# Power_Sheet.net
KiCad netlist of a schematic drawn in Altium Designer
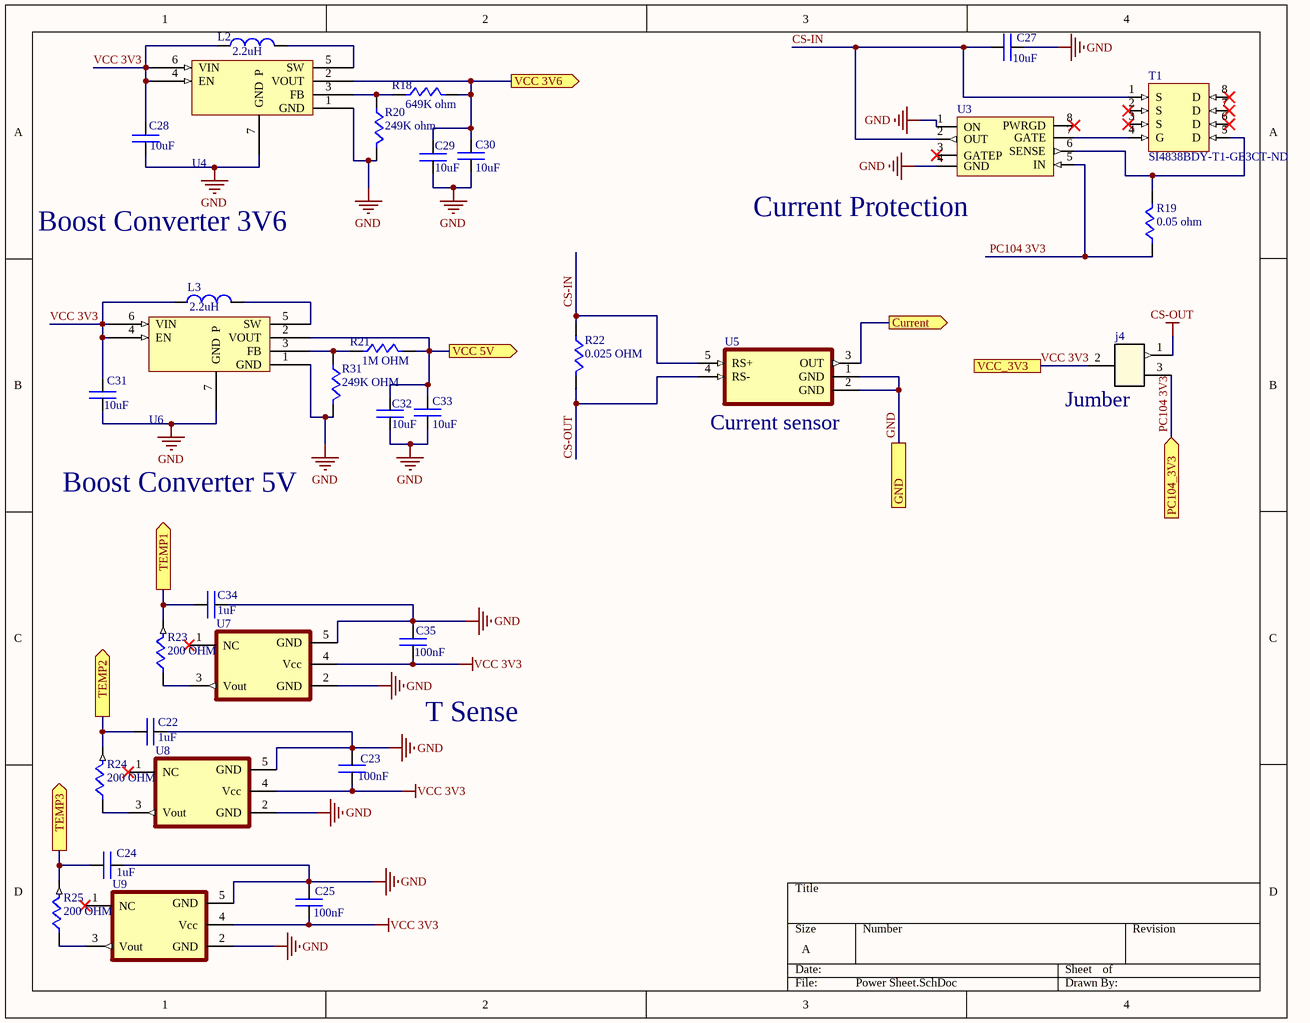
[diagram p0: Power Sheet.SchDoc]

(export (version "E")
  (design (tool "Eeschema 10.0.6"))
  (components
    (comp (ref "C22")
      (value "CAP CER 1UF 16V X7R 0805")
      (footprint "0805 C")
      (description "1µF ±5% 16V Ceramic Capacitor X7R 0805 (2012 Metric)")
      (fields
        (field (name "MANUFACTURER") "Murata")
        (field (name "MANUFACTURER PART NUMBER") "GRM219R61H105KA73D")
        (field (name "CAPACITANCE") "1uF")
      )
      (libsource (lib "comm sub") (part "C_1uF"))
    )
    (comp (ref "C23")
      (value "CAP CER 0.1UF 10V 0805")
      (footprint "0805 C")
      (description "0.1µF ±10% 16V Ceramic Capacitor X7R 0805 (2012 Metric)")
      (fields
        (field (name "MANUFACTURER") "Johanson")
        (field (name "MANUFACTURER PART NUMBER") "160R15W104KV4T")
        (field (name "CAPACITANCE") "100nF")
      )
      (libsource (lib "comm sub") (part "C_100nF"))
    )
    (comp (ref "C24")
      (value "CAP CER 1UF 16V X7R 0805")
      (footprint "0805 C")
      (description "1µF ±5% 16V Ceramic Capacitor X7R 0805 (2012 Metric)")
      (fields
        (field (name "MANUFACTURER") "Murata")
        (field (name "MANUFACTURER PART NUMBER") "GRM219R61H105KA73D")
        (field (name "CAPACITANCE") "1uF")
      )
      (libsource (lib "comm sub") (part "C_1uF"))
    )
    (comp (ref "C25")
      (value "CAP CER 0.1UF 10V 0805")
      (footprint "0805 C")
      (description "0.1µF ±10% 16V Ceramic Capacitor X7R 0805 (2012 Metric)")
      (fields
        (field (name "MANUFACTURER") "Johanson")
        (field (name "MANUFACTURER PART NUMBER") "160R15W104KV4T")
        (field (name "CAPACITANCE") "100nF")
      )
      (libsource (lib "comm sub") (part "C_100nF"))
    )
    (comp (ref "C27")
      (value "CAP CER 10UF 10V X5R 0805")
      (footprint "0805 C")
      (description "10µF ±10% 10V Ceramic Capacitor X5R 0805 (2012 Metric)")
      (fields
        (field (name "MANUFACTURER") "TDK")
        (field (name "MANUFACTURER PART NUMBER") "C2012X5R1C106K085AC")
        (field (name "CAPACITANCE") "10uF")
      )
      (libsource (lib "comm sub") (part "C_10uF"))
    )
    (comp (ref "C28")
      (value "CAP CER 10UF 10V X5R 0805")
      (footprint "0805 C")
      (description "10µF ±10% 10V Ceramic Capacitor X5R 0805 (2012 Metric)")
      (fields
        (field (name "MANUFACTURER") "TDK")
        (field (name "MANUFACTURER PART NUMBER") "C2012X5R1C106K085AC")
        (field (name "CAPACITANCE") "10uF")
      )
      (libsource (lib "comm sub") (part "C_10uF"))
    )
    (comp (ref "C29")
      (value "CAP CER 10UF 10V X5R 0805")
      (footprint "0805 C")
      (description "10µF ±10% 10V Ceramic Capacitor X5R 0805 (2012 Metric)")
      (fields
        (field (name "MANUFACTURER") "TDK")
        (field (name "MANUFACTURER PART NUMBER") "C2012X5R1C106K085AC")
        (field (name "CAPACITANCE") "10uF")
      )
      (libsource (lib "comm sub") (part "C_10uF"))
    )
    (comp (ref "C30")
      (value "CAP CER 10UF 10V X5R 0805")
      (footprint "0805 C")
      (description "10µF ±10% 10V Ceramic Capacitor X5R 0805 (2012 Metric)")
      (fields
        (field (name "MANUFACTURER") "TDK")
        (field (name "MANUFACTURER PART NUMBER") "C2012X5R1C106K085AC")
        (field (name "CAPACITANCE") "10uF")
      )
      (libsource (lib "comm sub") (part "C_10uF"))
    )
    (comp (ref "C31")
      (value "CAP CER 10UF 10V X5R 0805")
      (footprint "0805 C")
      (description "10µF ±10% 10V Ceramic Capacitor X5R 0805 (2012 Metric)")
      (fields
        (field (name "MANUFACTURER") "TDK")
        (field (name "MANUFACTURER PART NUMBER") "C2012X5R1C106K085AC")
        (field (name "CAPACITANCE") "10uF")
      )
      (libsource (lib "comm sub") (part "C_10uF"))
    )
    (comp (ref "C32")
      (value "CAP CER 10UF 10V X5R 0805")
      (footprint "0805 C")
      (description "10µF ±10% 10V Ceramic Capacitor X5R 0805 (2012 Metric)")
      (fields
        (field (name "MANUFACTURER") "TDK")
        (field (name "MANUFACTURER PART NUMBER") "C2012X5R1C106K085AC")
        (field (name "CAPACITANCE") "10uF")
      )
      (libsource (lib "comm sub") (part "C_10uF"))
    )
    (comp (ref "C33")
      (value "CAP CER 10UF 10V X5R 0805")
      (footprint "0805 C")
      (description "10µF ±10% 10V Ceramic Capacitor X5R 0805 (2012 Metric)")
      (fields
        (field (name "MANUFACTURER") "TDK")
        (field (name "MANUFACTURER PART NUMBER") "C2012X5R1C106K085AC")
        (field (name "CAPACITANCE") "10uF")
      )
      (libsource (lib "comm sub") (part "C_10uF"))
    )
    (comp (ref "C34")
      (value "CAP CER 1UF 16V X7R 0805")
      (footprint "0805 C")
      (description "1µF ±5% 16V Ceramic Capacitor X7R 0805 (2012 Metric)")
      (fields
        (field (name "MANUFACTURER") "Murata")
        (field (name "MANUFACTURER PART NUMBER") "GRM219R61H105KA73D")
        (field (name "CAPACITANCE") "1uF")
      )
      (libsource (lib "comm sub") (part "C_1uF"))
    )
    (comp (ref "C35")
      (value "CAP CER 0.1UF 10V 0805")
      (footprint "0805 C")
      (description "0.1µF ±10% 16V Ceramic Capacitor X7R 0805 (2012 Metric)")
      (fields
        (field (name "MANUFACTURER") "Johanson")
        (field (name "MANUFACTURER PART NUMBER") "160R15W104KV4T")
        (field (name "CAPACITANCE") "100nF")
      )
      (libsource (lib "comm sub") (part "C_100nF"))
    )
    (comp (ref "j4")
      (value "CONN HEADER VERT 3POS 2.54MM")
      (footprint "jumber")
      (description "Connector Header Through Hole 3 position 0.100\" (2.54mm)")
      (fields (field (name "MANUFACTURER") "Harwin") (field (name "MANUFACTURER PART NUMBER") "M20-9990345"))
      (libsource (lib "comm sub") (part "jumber"))
    )
    (comp (ref "L2")
      (value "FIXED IND 2.2UH 800MA 200 MOHM")
      (footprint "0805 L")
      (description "2.2µH Shielded Multilayer Inductor 800mA 200mOhm Max 0805 (2012 Metric)")
      (fields
        (field (name "MANUFACTURER") "Taiyo Yuden")
        (field (name "MANUFACTURER PART NUMBER") "BRC2012T2R2MD")
        (field (name "INDUCTANCE") "2.2uH")
      )
      (libsource (lib "comm sub") (part "L _2.2 uh"))
    )
    (comp (ref "L3")
      (value "FIXED IND 2.2UH 800MA 200 MOHM")
      (footprint "0805 L")
      (description "2.2µH Shielded Multilayer Inductor 800mA 200mOhm Max 0805 (2012 Metric)")
      (fields
        (field (name "MANUFACTURER") "Taiyo Yuden")
        (field (name "MANUFACTURER PART NUMBER") "BRC2012T2R2MD")
        (field (name "INDUCTANCE") "2.2uH")
      )
      (libsource (lib "comm sub") (part "L _2.2 uh"))
    )
    (comp (ref "R18")
      (value "649K ohm")
      (footprint "0805 R")
      (fields
        (field (name "MANUFACTURER") "Vishay")
        (field (name "MANUFACTURER PART NUMBER") "CRCW08050000Z0EAC")
        (field (name "TOLERANCE") "0.5%")
      )
      (libsource (lib "comm sub") (part "R_649k ohm"))
    )
    (comp (ref "R19")
      (value "0.05 ohm")
      (footprint "0805 R")
      (fields
        (field (name "MANUFACTURER") "Vishay")
        (field (name "MANUFACTURER PART NUMBER") "CRCW08050000Z0EAC")
        (field (name "TOLERANCE") "1%")
      )
      (libsource (lib "comm sub") (part "R_0.05ohm"))
    )
    (comp (ref "R20")
      (value "249K ohm")
      (footprint "0805 R")
      (fields
        (field (name "MANUFACTURER") "Vishay Dale")
        (field (name "MANUFACTURER PART NUMBER") "CRCW0805249KFKEAHP")
        (field (name "TOLERANCE") "1%")
      )
      (libsource (lib "comm sub") (part "R_249 kohm"))
    )
    (comp (ref "R21")
      (value "1M OHM")
      (footprint "0805 R")
      (fields
        (field (name "MANUFACTURER") "Vishay")
        (field (name "MANUFACTURER PART NUMBER") "CRCW08050000Z0EAC")
        (field (name "TOLERANCE") "1%")
      )
      (libsource (lib "comm sub") (part "R_1 Mohm"))
    )
    (comp (ref "R22")
      (value "0.025 OHM")
      (footprint "0805 R")
      (fields
        (field (name "MANUFACTURER") "Vishay")
        (field (name "MANUFACTURER PART NUMBER") "CRCW08050000Z0EAC")
      )
      (libsource (lib "comm sub") (part "R_0.025ohm"))
    )
    (comp (ref "R23")
      (value "200 OHM")
      (footprint "0805 R")
      (description "200 Ohms ±0.1% 0.125W, 1/8W Chip Resistor 0805 (2012 Metric) Automotive AEC-Q200 Thin Film")
      (fields
        (field (name "MANUFACTURER") "Panasonic")
        (field (name "MANUFACTURER PART NUMBER") "ERJ-P06F2000V")
      )
      (libsource (lib "comm sub") (part "R_200 ohm"))
    )
    (comp (ref "R24")
      (value "200 OHM")
      (footprint "0805 R")
      (description "200 Ohms ±0.1% 0.125W, 1/8W Chip Resistor 0805 (2012 Metric) Automotive AEC-Q200 Thin Film")
      (fields
        (field (name "MANUFACTURER") "Panasonic")
        (field (name "MANUFACTURER PART NUMBER") "ERJ-P06F2000V")
      )
      (libsource (lib "comm sub") (part "R_200 ohm"))
    )
    (comp (ref "R25")
      (value "200 OHM")
      (footprint "0805 R")
      (description "200 Ohms ±0.1% 0.125W, 1/8W Chip Resistor 0805 (2012 Metric) Automotive AEC-Q200 Thin Film")
      (fields
        (field (name "MANUFACTURER") "Panasonic")
        (field (name "MANUFACTURER PART NUMBER") "ERJ-P06F2000V")
      )
      (libsource (lib "comm sub") (part "R_200 ohm"))
    )
    (comp (ref "R31")
      (value "249K OHM")
      (footprint "0805 R")
      (fields
        (field (name "MANUFACTURER") "Vishay Dale")
        (field (name "MANUFACTURER PART NUMBER") "CRCW0805249KFKEAHP")
        (field (name "TOLERANCE") "1%")
      )
      (libsource (lib "comm sub") (part "R_249 kohm"))
    )
    (comp (ref "T1")
      (value "MOSFET N-CH 12V 34A 8-SOIC")
      (footprint "Transistor_MOSFET")
      (description "N-Channel 12V 34A (Tc) 2.5W (Ta), 5.7W (Tc) Surface Mount 8-SO")
      (fields
        (field (name "SUPPLIER PART NUMBER 1") "SI4838BDY-T1-GE3CT-ND")
        (field (name "MANUFACTURER") "Vishay Siliconix")
        (field (name "MANUFACTURER PART NUMBER") "SI4838BDY-T1-GE3")
      )
      (libsource (lib "comm sub") (part "Transistor_MOSFET"))
    )
    (comp (ref "U3")
      (value "IC OVERVOLTAGE/CUR PROT TSOT23-8")
      (footprint "current protection")
      (description "Handheld/Mobile Devices PMIC TSOT-23-8")
      (libsource (lib "comm sub") (part "current protection"))
    )
    (comp (ref "U4")
      (value "IC REG BOOST 3.6V 800MA 6WSON")
      (footprint "Booster converter")
      (description "Boost Switching Regulator IC Positive Fixed 3.6V 1 Output 800mA (Switch) 6-WDFN Exposed Pad")
      (libsource (lib "comm sub") (part "Boost converter"))
    )
    (comp (ref "U5")
      (value "IC CURR SENSE 1 CIRCUIT SOT23-5")
      (footprint "current sensor")
      (description "Current Sense Amplifier 1 Circuit  SOT-23-5")
      (fields (field (name "MP") "MAX9938FEUK+T") (field (name "MF") "Maxim Integrated"))
      (libsource (lib "comm sub") (part "current sensor"))
    )
    (comp (ref "U6")
      (value "IC REG BOOST 3.6V 800MA 6WSON")
      (footprint "Booster converter")
      (description "Boost Switching Regulator IC Positive Fixed 3.6V 1 Output 800mA (Switch) 6-WDFN Exposed Pad")
      (libsource (lib "comm sub") (part "Boost converter"))
    )
    (comp (ref "U7")
      (value "SENSOR ANALOG -55C-130C SOT323-5")
      (footprint "temperture sensor")
      (description "Temperature Sensor Analog, Local -55°C ~ 130°C 11.77mV/°C SOT-323-5")
      (fields (field (name "MP") "MAX9938FEUK+T") (field (name "MF") "Maxim Integrated"))
      (libsource (lib "comm sub") (part "Temperature sensor"))
    )
    (comp (ref "U8")
      (value "SENSOR ANALOG -55C-130C SOT323-5")
      (footprint "temperture sensor")
      (description "Temperature Sensor Analog, Local -55°C ~ 130°C 11.77mV/°C SOT-323-5")
      (fields (field (name "MP") "MAX9938FEUK+T") (field (name "MF") "Maxim Integrated"))
      (libsource (lib "comm sub") (part "Temperature sensor"))
    )
    (comp (ref "U9")
      (value "SENSOR ANALOG -55C-130C SOT323-5")
      (footprint "temperture sensor")
      (description "Temperature Sensor Analog, Local -55°C ~ 130°C 11.77mV/°C SOT-323-5")
      (fields (field (name "MP") "MAX9938FEUK+T") (field (name "MF") "Maxim Integrated"))
      (libsource (lib "comm sub") (part "Temperature sensor"))
    )
  )
  (nets
    (net (code "1") (name "/CS-IN") (class "Default")
      (node (ref "C27") (pin "2") (pinfunction "2_2") (pintype "passive"))
      (node (ref "R22") (pin "2") (pinfunction "2_2") (pintype "passive"))
      (node (ref "T1") (pin "1") (pinfunction "S_1") (pintype "input"))
      (node (ref "U3") (pin "2") (pinfunction "OUT_2") (pintype "output"))
      (node (ref "U5") (pin "5") (pinfunction "RS+_5") (pintype "input"))
    )
    (net (code "2") (name "/Current") (class "Default")
      (node (ref "U5") (pin "3") (pinfunction "OUT_3") (pintype "output"))
    )
    (net (code "3") (name "/PC104 3V3") (class "Default")
      (node (ref "R19") (pin "2") (pinfunction "2_2") (pintype "passive"))
      (node (ref "U3") (pin "5") (pinfunction "IN_5") (pintype "input"))
      (node (ref "j4") (pin "3") (pinfunction "3_3") (pintype "passive"))
    )
    (net (code "4") (name "/TEMP1") (class "Default")
      (node (ref "C34") (pin "1") (pinfunction "1_1") (pintype "passive"))
      (node (ref "R23") (pin "1") (pinfunction "1_1") (pintype "output"))
    )
    (net (code "5") (name "/TEMP2") (class "Default")
      (node (ref "C22") (pin "1") (pinfunction "1_1") (pintype "passive"))
      (node (ref "R24") (pin "1") (pinfunction "1_1") (pintype "output"))
    )
    (net (code "6") (name "/TEMP3") (class "Default")
      (node (ref "C24") (pin "1") (pinfunction "1_1") (pintype "passive"))
      (node (ref "R25") (pin "1") (pinfunction "1_1") (pintype "output"))
    )
    (net (code "7") (name "/VCC 3V6") (class "Default")
      (node (ref "C29") (pin "2") (pinfunction "2_2") (pintype "passive"))
      (node (ref "C30") (pin "2") (pinfunction "2_2") (pintype "passive"))
      (node (ref "R18") (pin "1") (pinfunction "1_1") (pintype "passive"))
      (node (ref "U4") (pin "2") (pinfunction "VOUT_2") (pintype "passive"))
    )
    (net (code "8") (name "/VCC 5V") (class "Default")
      (node (ref "C32") (pin "2") (pinfunction "2_2") (pintype "passive"))
      (node (ref "C33") (pin "2") (pinfunction "2_2") (pintype "passive"))
      (node (ref "R21") (pin "1") (pinfunction "1_1") (pintype "passive"))
      (node (ref "U6") (pin "2") (pinfunction "VOUT_2") (pintype "passive"))
    )
    (net (code "9") (name "CS-OUT") (class "Default")
      (node (ref "R22") (pin "1") (pinfunction "1_1") (pintype "passive"))
      (node (ref "U5") (pin "4") (pinfunction "RS-_4") (pintype "input"))
      (node (ref "j4") (pin "1") (pinfunction "1_1") (pintype "output"))
    )
    (net (code "10") (name "GND") (class "Default")
      (node (ref "C22") (pin "2") (pinfunction "2_2") (pintype "passive"))
      (node (ref "C23") (pin "1") (pinfunction "1_1") (pintype "passive"))
      (node (ref "C24") (pin "2") (pinfunction "2_2") (pintype "passive"))
      (node (ref "C25") (pin "1") (pinfunction "1_1") (pintype "passive"))
      (node (ref "C27") (pin "1") (pinfunction "1_1") (pintype "passive"))
      (node (ref "C28") (pin "2") (pinfunction "2_2") (pintype "passive"))
      (node (ref "C29") (pin "1") (pinfunction "1_1") (pintype "passive"))
      (node (ref "C30") (pin "1") (pinfunction "1_1") (pintype "passive"))
      (node (ref "C31") (pin "2") (pinfunction "2_2") (pintype "passive"))
      (node (ref "C32") (pin "1") (pinfunction "1_1") (pintype "passive"))
      (node (ref "C33") (pin "1") (pinfunction "1_1") (pintype "passive"))
      (node (ref "C34") (pin "2") (pinfunction "2_2") (pintype "passive"))
      (node (ref "C35") (pin "1") (pinfunction "1_1") (pintype "passive"))
      (node (ref "R20") (pin "1") (pinfunction "1_1") (pintype "passive"))
      (node (ref "R31") (pin "1") (pinfunction "1_1") (pintype "passive"))
      (node (ref "U3") (pin "1") (pinfunction "ON_1") (pintype "passive"))
      (node (ref "U3") (pin "4") (pinfunction "GND_4") (pintype "power_in"))
      (node (ref "U4") (pin "1") (pinfunction "GND_1") (pintype "power_in"))
      (node (ref "U4") (pin "7") (pinfunction "GND__P_7") (pintype "power_in"))
      (node (ref "U5") (pin "1") (pinfunction "GND_1") (pintype "power_in"))
      (node (ref "U5") (pin "2") (pinfunction "GND_2") (pintype "power_in"))
      (node (ref "U6") (pin "1") (pinfunction "GND_1") (pintype "power_in"))
      (node (ref "U6") (pin "7") (pinfunction "GND__P_7") (pintype "power_in"))
      (node (ref "U7") (pin "2") (pinfunction "GND_2") (pintype "power_in"))
      (node (ref "U7") (pin "5") (pinfunction "GND_5") (pintype "power_in"))
      (node (ref "U8") (pin "2") (pinfunction "GND_2") (pintype "power_in"))
      (node (ref "U8") (pin "5") (pinfunction "GND_5") (pintype "power_in"))
      (node (ref "U9") (pin "2") (pinfunction "GND_2") (pintype "power_in"))
      (node (ref "U9") (pin "5") (pinfunction "GND_5") (pintype "power_in"))
    )
    (net (code "11") (name "Net-(T1-G)") (class "Default")
      (node (ref "T1") (pin "4") (pinfunction "G_4") (pintype "input"))
      (node (ref "U3") (pin "7") (pinfunction "GATE_7") (pintype "power_in"))
    )
    (net (code "12") (name "Net-(U3-SENSE)") (class "Default")
      (node (ref "R19") (pin "1") (pinfunction "1_1") (pintype "passive"))
      (node (ref "T1") (pin "5") (pinfunction "D_5") (pintype "input"))
      (node (ref "U3") (pin "6") (pinfunction "SENSE_6") (pintype "output"))
    )
    (net (code "13") (name "Net-(U4-FB)") (class "Default")
      (node (ref "R18") (pin "2") (pinfunction "2_2") (pintype "passive"))
      (node (ref "R20") (pin "2") (pinfunction "2_2") (pintype "passive"))
      (node (ref "U4") (pin "3") (pinfunction "FB_3") (pintype "power_in"))
    )
    (net (code "14") (name "Net-(U4-SW)") (class "Default")
      (node (ref "L2") (pin "1") (pintype "passive"))
      (node (ref "U4") (pin "5") (pinfunction "SW_5") (pintype "power_in"))
    )
    (net (code "15") (name "Net-(U6-FB)") (class "Default")
      (node (ref "R21") (pin "2") (pinfunction "2_2") (pintype "passive"))
      (node (ref "R31") (pin "2") (pinfunction "2_2") (pintype "passive"))
      (node (ref "U6") (pin "3") (pinfunction "FB_3") (pintype "power_in"))
    )
    (net (code "16") (name "Net-(U6-SW)") (class "Default")
      (node (ref "L3") (pin "1") (pintype "passive"))
      (node (ref "U6") (pin "5") (pinfunction "SW_5") (pintype "power_in"))
    )
    (net (code "17") (name "Net-(U7-Vout)") (class "Default")
      (node (ref "R23") (pin "2") (pinfunction "2_2") (pintype "passive"))
      (node (ref "U7") (pin "3") (pinfunction "Vout_3") (pintype "output"))
    )
    (net (code "18") (name "Net-(U8-Vout)") (class "Default")
      (node (ref "R24") (pin "2") (pinfunction "2_2") (pintype "passive"))
      (node (ref "U8") (pin "3") (pinfunction "Vout_3") (pintype "output"))
    )
    (net (code "19") (name "Net-(U9-Vout)") (class "Default")
      (node (ref "R25") (pin "2") (pinfunction "2_2") (pintype "passive"))
      (node (ref "U9") (pin "3") (pinfunction "Vout_3") (pintype "output"))
    )
    (net (code "20") (name "VCC 3V3") (class "Default")
      (node (ref "C23") (pin "2") (pinfunction "2_2") (pintype "passive"))
      (node (ref "C25") (pin "2") (pinfunction "2_2") (pintype "passive"))
      (node (ref "C28") (pin "1") (pinfunction "1_1") (pintype "passive"))
      (node (ref "C31") (pin "1") (pinfunction "1_1") (pintype "passive"))
      (node (ref "C35") (pin "2") (pinfunction "2_2") (pintype "passive"))
      (node (ref "L2") (pin "2") (pinfunction "2_2") (pintype "passive"))
      (node (ref "L3") (pin "2") (pinfunction "2_2") (pintype "passive"))
      (node (ref "U4") (pin "4") (pinfunction "EN_4") (pintype "input"))
      (node (ref "U4") (pin "6") (pinfunction "VIN_6") (pintype "input"))
      (node (ref "U6") (pin "4") (pinfunction "EN_4") (pintype "input"))
      (node (ref "U6") (pin "6") (pinfunction "VIN_6") (pintype "input"))
      (node (ref "U7") (pin "4") (pinfunction "Vcc_4") (pintype "power_in"))
      (node (ref "U8") (pin "4") (pinfunction "Vcc_4") (pintype "power_in"))
      (node (ref "U9") (pin "4") (pinfunction "Vcc_4") (pintype "power_in"))
      (node (ref "j4") (pin "2") (pinfunction "2_2") (pintype "passive"))
    )
    (net (code "21") (name "unconnected-(T1-D-Pad6)") (class "Default")
      (node (ref "T1") (pin "6") (pinfunction "D_6") (pintype "input+no_connect"))
    )
    (net (code "22") (name "unconnected-(T1-D-Pad7)") (class "Default")
      (node (ref "T1") (pin "7") (pinfunction "D_7") (pintype "input+no_connect"))
    )
    (net (code "23") (name "unconnected-(T1-D-Pad8)") (class "Default")
      (node (ref "T1") (pin "8") (pinfunction "D_8") (pintype "input+no_connect"))
    )
    (net (code "24") (name "unconnected-(T1-S-Pad2)") (class "Default")
      (node (ref "T1") (pin "2") (pinfunction "S_2") (pintype "input+no_connect"))
    )
    (net (code "25") (name "unconnected-(T1-S-Pad3)") (class "Default")
      (node (ref "T1") (pin "3") (pinfunction "S_3") (pintype "input+no_connect"))
    )
    (net (code "26") (name "unconnected-(U3-GATEP-Pad3)") (class "Default")
      (node (ref "U3") (pin "3") (pinfunction "GATEP_3") (pintype "power_in+no_connect"))
    )
    (net (code "27") (name "unconnected-(U3-PWRGD-Pad8)") (class "Default")
      (node (ref "U3") (pin "8") (pinfunction "PWRGD_8") (pintype "power_in+no_connect"))
    )
    (net (code "28") (name "unconnected-(U7-NC-Pad1)") (class "Default")
      (node (ref "U7") (pin "1") (pinfunction "NC_1") (pintype "power_in+no_connect"))
    )
    (net (code "29") (name "unconnected-(U8-NC-Pad1)") (class "Default")
      (node (ref "U8") (pin "1") (pinfunction "NC_1") (pintype "power_in+no_connect"))
    )
    (net (code "30") (name "unconnected-(U9-NC-Pad1)") (class "Default")
      (node (ref "U9") (pin "1") (pinfunction "NC_1") (pintype "power_in+no_connect"))
    )
  )
)
